# EDM_switch.net
KiCad netlist of a schematic drawn in EAGLE
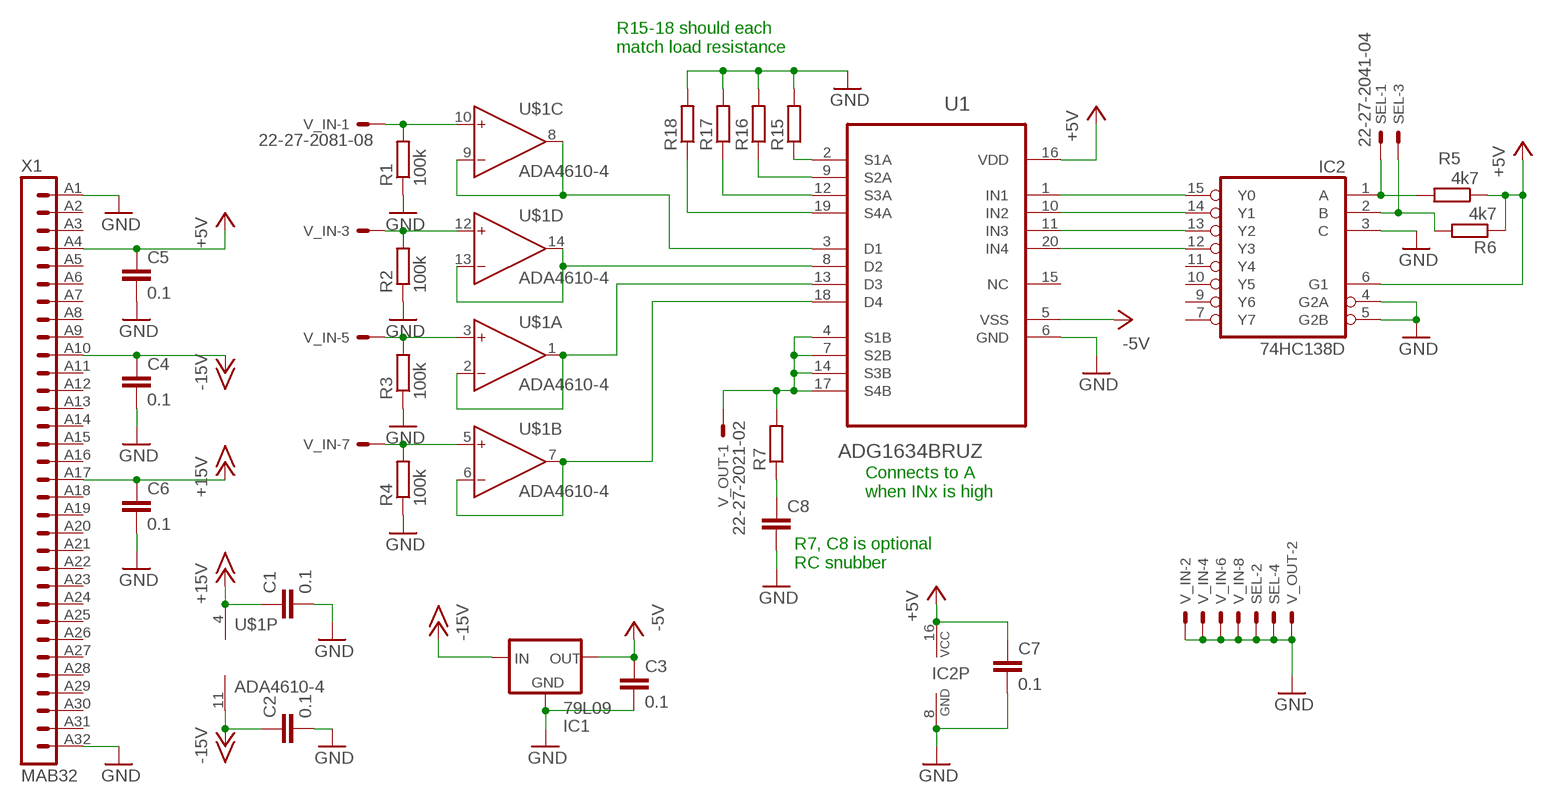
[diagram p0: schematic, sheet 1]

(export (version "E")
  (design (tool "Eeschema 10.0.6"))
  (components
    (comp (ref "C1")
      (value "0.1")
      (footprint "eagle-import:C0805")
      (libsource (lib "eagle-import") (part "C-EUC0805"))
    )
    (comp (ref "C2")
      (value "0.1")
      (footprint "eagle-import:C0805")
      (libsource (lib "eagle-import") (part "C-EUC0805"))
    )
    (comp (ref "C3")
      (value "0.1")
      (footprint "eagle-import:C0805")
      (libsource (lib "eagle-import") (part "C-EUC0805"))
    )
    (comp (ref "C4")
      (value "0.1")
      (footprint "eagle-import:C0805")
      (libsource (lib "eagle-import") (part "C-EUC0805"))
    )
    (comp (ref "C5")
      (value "0.1")
      (footprint "eagle-import:C0805")
      (libsource (lib "eagle-import") (part "C-EUC0805"))
    )
    (comp (ref "C6")
      (value "0.1")
      (footprint "eagle-import:C0805")
      (libsource (lib "eagle-import") (part "C-EUC0805"))
    )
    (comp (ref "C7")
      (value "0.1")
      (footprint "eagle-import:C0805")
      (libsource (lib "eagle-import") (part "C-EUC0805"))
    )
    (comp (ref "C8")
      (value "C-EUC0805")
      (footprint "eagle-import:C0805")
      (libsource (lib "eagle-import") (part "C-EUC0805"))
    )
    (comp (ref "IC1")
      (value "79L09")
      (footprint "eagle-import:79LXX")
      (libsource (lib "eagle-import") (part "79LXX"))
    )
    (comp (ref "IC2")
      (value "74HC138D")
      (footprint "eagle-import:SO16")
      (libsource (lib "eagle-import") (part "74138DHC"))
    )
    (comp (ref "R1")
      (value "100k")
      (footprint "eagle-import:R0805")
      (libsource (lib "eagle-import") (part "R-EU_R0805"))
    )
    (comp (ref "R2")
      (value "100k")
      (footprint "eagle-import:R0805")
      (libsource (lib "eagle-import") (part "R-EU_R0805"))
    )
    (comp (ref "R3")
      (value "100k")
      (footprint "eagle-import:R0805")
      (libsource (lib "eagle-import") (part "R-EU_R0805"))
    )
    (comp (ref "R4")
      (value "100k")
      (footprint "eagle-import:R0805")
      (libsource (lib "eagle-import") (part "R-EU_R0805"))
    )
    (comp (ref "R5")
      (value "4k7")
      (footprint "eagle-import:R0805")
      (libsource (lib "eagle-import") (part "R-EU_R0805"))
    )
    (comp (ref "R6")
      (value "4k7")
      (footprint "eagle-import:R0805")
      (libsource (lib "eagle-import") (part "R-EU_R0805"))
    )
    (comp (ref "R7")
      (value "R-EU_R0805")
      (footprint "eagle-import:R0805")
      (libsource (lib "eagle-import") (part "R-EU_R0805"))
    )
    (comp (ref "R15")
      (value "R-EU_0204/7")
      (footprint "eagle-import:0204_7")
      (libsource (lib "eagle-import") (part "R-EU_0204/7"))
    )
    (comp (ref "R16")
      (value "R-EU_0204/7")
      (footprint "eagle-import:0204_7")
      (libsource (lib "eagle-import") (part "R-EU_0204/7"))
    )
    (comp (ref "R17")
      (value "R-EU_0204/7")
      (footprint "eagle-import:0204_7")
      (libsource (lib "eagle-import") (part "R-EU_0204/7"))
    )
    (comp (ref "R18")
      (value "R-EU_0204/7")
      (footprint "eagle-import:0204_7")
      (libsource (lib "eagle-import") (part "R-EU_0204/7"))
    )
    (comp (ref "SEL")
      (value "22-27-2041-04")
      (footprint "eagle-import:6410-04")
      (libsource (lib "eagle-import") (part "22-?-0427-2041"))
    )
    (comp (ref "U$1")
      (value "ADA4610-4")
      (footprint "eagle-import:SO14")
      (libsource (lib "eagle-import") (part "ADA4610-4"))
    )
    (comp (ref "U1")
      (value "ADG1634BRUZ")
      (footprint "eagle-import:SOP65P640X120-20N")
      (libsource (lib "eagle-import") (part "ADG1634BRUZ"))
    )
    (comp (ref "V_IN")
      (value "22-27-2081-08")
      (footprint "eagle-import:6410-08")
      (libsource (lib "eagle-import") (part "22-?-0827-2081"))
    )
    (comp (ref "V_OUT")
      (value "22-27-2021-02")
      (footprint "eagle-import:6410-02")
      (libsource (lib "eagle-import") (part "22-?-0227-2021"))
    )
    (comp (ref "X1")
      (value "MAB32")
      (footprint "eagle-import:MAB32")
      (libsource (lib "eagle-import") (part "MAB32"))
    )
  )
  (nets
    (net (code "1") (name "+5V") (class "Default")
      (node (ref "C5") (pin "1") (pinfunction "1_1") (pintype "passive"))
      (node (ref "C7") (pin "1") (pinfunction "1_1") (pintype "passive"))
      (node (ref "IC2") (pin "16") (pinfunction "VCC_16") (pintype "power_in"))
      (node (ref "IC2") (pin "6") (pinfunction "G1_6") (pintype "input"))
      (node (ref "R5") (pin "1") (pinfunction "1_1") (pintype "passive"))
      (node (ref "R6") (pin "1") (pinfunction "1_1") (pintype "passive"))
      (node (ref "U1") (pin "16") (pinfunction "VDD_16") (pintype "power_in"))
      (node (ref "X1") (pin "A4") (pinfunction "4_A4") (pintype "passive"))
    )
    (net (code "2") (name "+15V") (class "Default")
      (node (ref "C1") (pin "1") (pinfunction "1_1") (pintype "passive"))
      (node (ref "C6") (pin "1") (pinfunction "1_1") (pintype "passive"))
      (node (ref "U$1") (pin "4") (pinfunction "V+_4") (pintype "power_in"))
      (node (ref "X1") (pin "A17") (pinfunction "17_A17") (pintype "passive"))
    )
    (net (code "3") (name "-5V") (class "Default")
      (node (ref "C3") (pin "1") (pinfunction "1_1") (pintype "passive"))
      (node (ref "IC1") (pin "OUT") (pinfunction "OUT_OUT") (pintype "passive"))
      (node (ref "U1") (pin "5") (pinfunction "VSS_5") (pintype "power_in"))
    )
    (net (code "4") (name "-15V") (class "Default")
      (node (ref "C2") (pin "1") (pinfunction "1_1") (pintype "passive"))
      (node (ref "C4") (pin "1") (pinfunction "1_1") (pintype "passive"))
      (node (ref "IC1") (pin "IN") (pinfunction "IN_IN") (pintype "input"))
      (node (ref "U$1") (pin "11") (pinfunction "V-_11") (pintype "power_in"))
      (node (ref "X1") (pin "A10") (pinfunction "10_A10") (pintype "passive"))
    )
    (net (code "5") (name "GND") (class "Default")
      (node (ref "C1") (pin "2") (pinfunction "2_2") (pintype "passive"))
      (node (ref "C2") (pin "2") (pinfunction "2_2") (pintype "passive"))
      (node (ref "C3") (pin "2") (pinfunction "2_2") (pintype "passive"))
      (node (ref "C4") (pin "2") (pinfunction "2_2") (pintype "passive"))
      (node (ref "C5") (pin "2") (pinfunction "2_2") (pintype "passive"))
      (node (ref "C6") (pin "2") (pinfunction "2_2") (pintype "passive"))
      (node (ref "C7") (pin "2") (pinfunction "2_2") (pintype "passive"))
      (node (ref "C8") (pin "2") (pinfunction "2_2") (pintype "passive"))
      (node (ref "IC1") (pin "GND") (pinfunction "GND_GND") (pintype "input"))
      (node (ref "IC2") (pin "3") (pinfunction "C_3") (pintype "input"))
      (node (ref "IC2") (pin "4") (pinfunction "G2A_4") (pintype "input"))
      (node (ref "IC2") (pin "5") (pinfunction "G2B_5") (pintype "input"))
      (node (ref "IC2") (pin "8") (pinfunction "GND_8") (pintype "power_in"))
      (node (ref "R1") (pin "1") (pinfunction "1_1") (pintype "passive"))
      (node (ref "R15") (pin "2") (pinfunction "2_2") (pintype "passive"))
      (node (ref "R16") (pin "2") (pinfunction "2_2") (pintype "passive"))
      (node (ref "R17") (pin "2") (pinfunction "2_2") (pintype "passive"))
      (node (ref "R18") (pin "2") (pinfunction "2_2") (pintype "passive"))
      (node (ref "R2") (pin "1") (pinfunction "1_1") (pintype "passive"))
      (node (ref "R3") (pin "1") (pinfunction "1_1") (pintype "passive"))
      (node (ref "R4") (pin "1") (pinfunction "1_1") (pintype "passive"))
      (node (ref "SEL") (pin "2") (pinfunction "S_2") (pintype "passive"))
      (node (ref "SEL") (pin "4") (pinfunction "S_4") (pintype "passive"))
      (node (ref "U1") (pin "6") (pinfunction "GND_6") (pintype "passive"))
      (node (ref "V_IN") (pin "2") (pinfunction "S_2") (pintype "passive"))
      (node (ref "V_IN") (pin "4") (pinfunction "S_4") (pintype "passive"))
      (node (ref "V_IN") (pin "6") (pinfunction "S_6") (pintype "passive"))
      (node (ref "V_IN") (pin "8") (pinfunction "S_8") (pintype "passive"))
      (node (ref "V_OUT") (pin "2") (pinfunction "S_2") (pintype "passive"))
      (node (ref "X1") (pin "A1") (pinfunction "1_A1") (pintype "passive"))
      (node (ref "X1") (pin "A32") (pinfunction "32_A32") (pintype "passive"))
    )
    (net (code "6") (name "Net-(C8-Pad1)") (class "Default")
      (node (ref "C8") (pin "1") (pinfunction "1_1") (pintype "passive"))
      (node (ref "R7") (pin "1") (pinfunction "1_1") (pintype "passive"))
    )
    (net (code "7") (name "Net-(IC2A-A)") (class "Default")
      (node (ref "IC2") (pin "1") (pinfunction "A_1") (pintype "input"))
      (node (ref "R5") (pin "2") (pinfunction "2_2") (pintype "passive"))
      (node (ref "SEL") (pin "1") (pinfunction "S_1") (pintype "passive"))
    )
    (net (code "8") (name "Net-(IC2A-B)") (class "Default")
      (node (ref "IC2") (pin "2") (pinfunction "B_2") (pintype "input"))
      (node (ref "R6") (pin "2") (pinfunction "2_2") (pintype "passive"))
      (node (ref "SEL") (pin "3") (pinfunction "S_3") (pintype "passive"))
    )
    (net (code "9") (name "Net-(IC2A-Y0)") (class "Default")
      (node (ref "IC2") (pin "15") (pinfunction "Y0_15") (pintype "output"))
      (node (ref "U1") (pin "1") (pinfunction "IN1_1") (pintype "input"))
    )
    (net (code "10") (name "Net-(IC2A-Y1)") (class "Default")
      (node (ref "IC2") (pin "14") (pinfunction "Y1_14") (pintype "output"))
      (node (ref "U1") (pin "10") (pinfunction "IN2_10") (pintype "input"))
    )
    (net (code "11") (name "Net-(IC2A-Y2)") (class "Default")
      (node (ref "IC2") (pin "13") (pinfunction "Y2_13") (pintype "output"))
      (node (ref "U1") (pin "11") (pinfunction "IN3_11") (pintype "input"))
    )
    (net (code "12") (name "Net-(IC2A-Y3)") (class "Default")
      (node (ref "IC2") (pin "12") (pinfunction "Y3_12") (pintype "output"))
      (node (ref "U1") (pin "20") (pinfunction "IN4_20") (pintype "input"))
    )
    (net (code "13") (name "Net-(U$1A-IN+)") (class "Default")
      (node (ref "R3") (pin "2") (pinfunction "2_2") (pintype "passive"))
      (node (ref "U$1") (pin "3") (pinfunction "IN+_3") (pintype "input"))
      (node (ref "V_IN") (pin "5") (pinfunction "S_5") (pintype "passive"))
    )
    (net (code "14") (name "Net-(U$1A-IN-)") (class "Default")
      (node (ref "U$1") (pin "1") (pinfunction "OUT_1") (pintype "output"))
      (node (ref "U$1") (pin "2") (pinfunction "IN-_2") (pintype "input"))
      (node (ref "U1") (pin "13") (pinfunction "D3_13") (pintype "output"))
    )
    (net (code "15") (name "Net-(U$1B-IN+)") (class "Default")
      (node (ref "R4") (pin "2") (pinfunction "2_2") (pintype "passive"))
      (node (ref "U$1") (pin "5") (pinfunction "IN+_5") (pintype "input"))
      (node (ref "V_IN") (pin "7") (pinfunction "S_7") (pintype "passive"))
    )
    (net (code "16") (name "Net-(U$1B-IN-)") (class "Default")
      (node (ref "U$1") (pin "6") (pinfunction "IN-_6") (pintype "input"))
      (node (ref "U$1") (pin "7") (pinfunction "OUT_7") (pintype "output"))
      (node (ref "U1") (pin "18") (pinfunction "D4_18") (pintype "output"))
    )
    (net (code "17") (name "Net-(U$1C-IN+)") (class "Default")
      (node (ref "R1") (pin "2") (pinfunction "2_2") (pintype "passive"))
      (node (ref "U$1") (pin "10") (pinfunction "IN+_10") (pintype "input"))
      (node (ref "V_IN") (pin "1") (pinfunction "S_1") (pintype "passive"))
    )
    (net (code "18") (name "Net-(U$1C-IN-)") (class "Default")
      (node (ref "U$1") (pin "8") (pinfunction "OUT_8") (pintype "output"))
      (node (ref "U$1") (pin "9") (pinfunction "IN-_9") (pintype "input"))
      (node (ref "U1") (pin "3") (pinfunction "D1_3") (pintype "output"))
    )
    (net (code "19") (name "Net-(U$1D-IN+)") (class "Default")
      (node (ref "R2") (pin "2") (pinfunction "2_2") (pintype "passive"))
      (node (ref "U$1") (pin "12") (pinfunction "IN+_12") (pintype "input"))
      (node (ref "V_IN") (pin "3") (pinfunction "S_3") (pintype "passive"))
    )
    (net (code "20") (name "Net-(U$1D-IN-)") (class "Default")
      (node (ref "U$1") (pin "13") (pinfunction "IN-_13") (pintype "input"))
      (node (ref "U$1") (pin "14") (pinfunction "OUT_14") (pintype "output"))
      (node (ref "U1") (pin "8") (pinfunction "D2_8") (pintype "output"))
    )
    (net (code "21") (name "Net-(U1-S1A)") (class "Default")
      (node (ref "R15") (pin "1") (pinfunction "1_1") (pintype "passive"))
      (node (ref "U1") (pin "2") (pinfunction "S1A_2") (pintype "output"))
    )
    (net (code "22") (name "Net-(U1-S1B)") (class "Default")
      (node (ref "R7") (pin "2") (pinfunction "2_2") (pintype "passive"))
      (node (ref "U1") (pin "14") (pinfunction "S3B_14") (pintype "output"))
      (node (ref "U1") (pin "17") (pinfunction "S4B_17") (pintype "output"))
      (node (ref "U1") (pin "4") (pinfunction "S1B_4") (pintype "output"))
      (node (ref "U1") (pin "7") (pinfunction "S2B_7") (pintype "output"))
      (node (ref "V_OUT") (pin "1") (pinfunction "S_1") (pintype "passive"))
    )
    (net (code "23") (name "Net-(U1-S2A)") (class "Default")
      (node (ref "R16") (pin "1") (pinfunction "1_1") (pintype "passive"))
      (node (ref "U1") (pin "9") (pinfunction "S2A_9") (pintype "output"))
    )
    (net (code "24") (name "Net-(U1-S3A)") (class "Default")
      (node (ref "R17") (pin "1") (pinfunction "1_1") (pintype "passive"))
      (node (ref "U1") (pin "12") (pinfunction "S3A_12") (pintype "output"))
    )
    (net (code "25") (name "Net-(U1-S4A)") (class "Default")
      (node (ref "R18") (pin "1") (pinfunction "1_1") (pintype "passive"))
      (node (ref "U1") (pin "19") (pinfunction "S4A_19") (pintype "output"))
    )
    (net (code "26") (name "unconnected-(IC2A-Y4-Pad11)") (class "Default")
      (node (ref "IC2") (pin "11") (pinfunction "Y4_11") (pintype "output"))
    )
    (net (code "27") (name "unconnected-(IC2A-Y5-Pad10)") (class "Default")
      (node (ref "IC2") (pin "10") (pinfunction "Y5_10") (pintype "output"))
    )
    (net (code "28") (name "unconnected-(IC2A-Y6-Pad9)") (class "Default")
      (node (ref "IC2") (pin "9") (pinfunction "Y6_9") (pintype "output"))
    )
    (net (code "29") (name "unconnected-(IC2A-Y7-Pad7)") (class "Default")
      (node (ref "IC2") (pin "7") (pinfunction "Y7_7") (pintype "output"))
    )
    (net (code "30") (name "unconnected-(U1-NC-Pad15)") (class "Default")
      (node (ref "U1") (pin "15") (pinfunction "NC_15") (pintype "no_connect"))
    )
    (net (code "31") (name "unconnected-(X1-2-PadA2)") (class "Default")
      (node (ref "X1") (pin "A2") (pinfunction "2_A2") (pintype "passive"))
    )
    (net (code "32") (name "unconnected-(X1-3-PadA3)") (class "Default")
      (node (ref "X1") (pin "A3") (pinfunction "3_A3") (pintype "passive"))
    )
    (net (code "33") (name "unconnected-(X1-5-PadA5)") (class "Default")
      (node (ref "X1") (pin "A5") (pinfunction "5_A5") (pintype "passive"))
    )
    (net (code "34") (name "unconnected-(X1-6-PadA6)") (class "Default")
      (node (ref "X1") (pin "A6") (pinfunction "6_A6") (pintype "passive"))
    )
    (net (code "35") (name "unconnected-(X1-7-PadA7)") (class "Default")
      (node (ref "X1") (pin "A7") (pinfunction "7_A7") (pintype "passive"))
    )
    (net (code "36") (name "unconnected-(X1-8-PadA8)") (class "Default")
      (node (ref "X1") (pin "A8") (pinfunction "8_A8") (pintype "passive"))
    )
    (net (code "37") (name "unconnected-(X1-9-PadA9)") (class "Default")
      (node (ref "X1") (pin "A9") (pinfunction "9_A9") (pintype "passive"))
    )
    (net (code "38") (name "unconnected-(X1-11-PadA11)") (class "Default")
      (node (ref "X1") (pin "A11") (pinfunction "11_A11") (pintype "passive"))
    )
    (net (code "39") (name "unconnected-(X1-12-PadA12)") (class "Default")
      (node (ref "X1") (pin "A12") (pinfunction "12_A12") (pintype "passive"))
    )
    (net (code "40") (name "unconnected-(X1-13-PadA13)") (class "Default")
      (node (ref "X1") (pin "A13") (pinfunction "13_A13") (pintype "passive"))
    )
    (net (code "41") (name "unconnected-(X1-14-PadA14)") (class "Default")
      (node (ref "X1") (pin "A14") (pinfunction "14_A14") (pintype "passive"))
    )
    (net (code "42") (name "unconnected-(X1-15-PadA15)") (class "Default")
      (node (ref "X1") (pin "A15") (pinfunction "15_A15") (pintype "passive"))
    )
    (net (code "43") (name "unconnected-(X1-16-PadA16)") (class "Default")
      (node (ref "X1") (pin "A16") (pinfunction "16_A16") (pintype "passive"))
    )
    (net (code "44") (name "unconnected-(X1-18-PadA18)") (class "Default")
      (node (ref "X1") (pin "A18") (pinfunction "18_A18") (pintype "passive"))
    )
    (net (code "45") (name "unconnected-(X1-19-PadA19)") (class "Default")
      (node (ref "X1") (pin "A19") (pinfunction "19_A19") (pintype "passive"))
    )
    (net (code "46") (name "unconnected-(X1-20-PadA20)") (class "Default")
      (node (ref "X1") (pin "A20") (pinfunction "20_A20") (pintype "passive"))
    )
    (net (code "47") (name "unconnected-(X1-21-PadA21)") (class "Default")
      (node (ref "X1") (pin "A21") (pinfunction "21_A21") (pintype "passive"))
    )
    (net (code "48") (name "unconnected-(X1-22-PadA22)") (class "Default")
      (node (ref "X1") (pin "A22") (pinfunction "22_A22") (pintype "passive"))
    )
    (net (code "49") (name "unconnected-(X1-23-PadA23)") (class "Default")
      (node (ref "X1") (pin "A23") (pinfunction "23_A23") (pintype "passive"))
    )
    (net (code "50") (name "unconnected-(X1-24-PadA24)") (class "Default")
      (node (ref "X1") (pin "A24") (pinfunction "24_A24") (pintype "passive"))
    )
    (net (code "51") (name "unconnected-(X1-25-PadA25)") (class "Default")
      (node (ref "X1") (pin "A25") (pinfunction "25_A25") (pintype "passive"))
    )
    (net (code "52") (name "unconnected-(X1-26-PadA26)") (class "Default")
      (node (ref "X1") (pin "A26") (pinfunction "26_A26") (pintype "passive"))
    )
    (net (code "53") (name "unconnected-(X1-27-PadA27)") (class "Default")
      (node (ref "X1") (pin "A27") (pinfunction "27_A27") (pintype "passive"))
    )
    (net (code "54") (name "unconnected-(X1-28-PadA28)") (class "Default")
      (node (ref "X1") (pin "A28") (pinfunction "28_A28") (pintype "passive"))
    )
    (net (code "55") (name "unconnected-(X1-29-PadA29)") (class "Default")
      (node (ref "X1") (pin "A29") (pinfunction "29_A29") (pintype "passive"))
    )
    (net (code "56") (name "unconnected-(X1-30-PadA30)") (class "Default")
      (node (ref "X1") (pin "A30") (pinfunction "30_A30") (pintype "passive"))
    )
    (net (code "57") (name "unconnected-(X1-31-PadA31)") (class "Default")
      (node (ref "X1") (pin "A31") (pinfunction "31_A31") (pintype "passive"))
    )
  )
)
